# Digital_Input2.net
KiCad netlist of a schematic drawn in Altium Designer
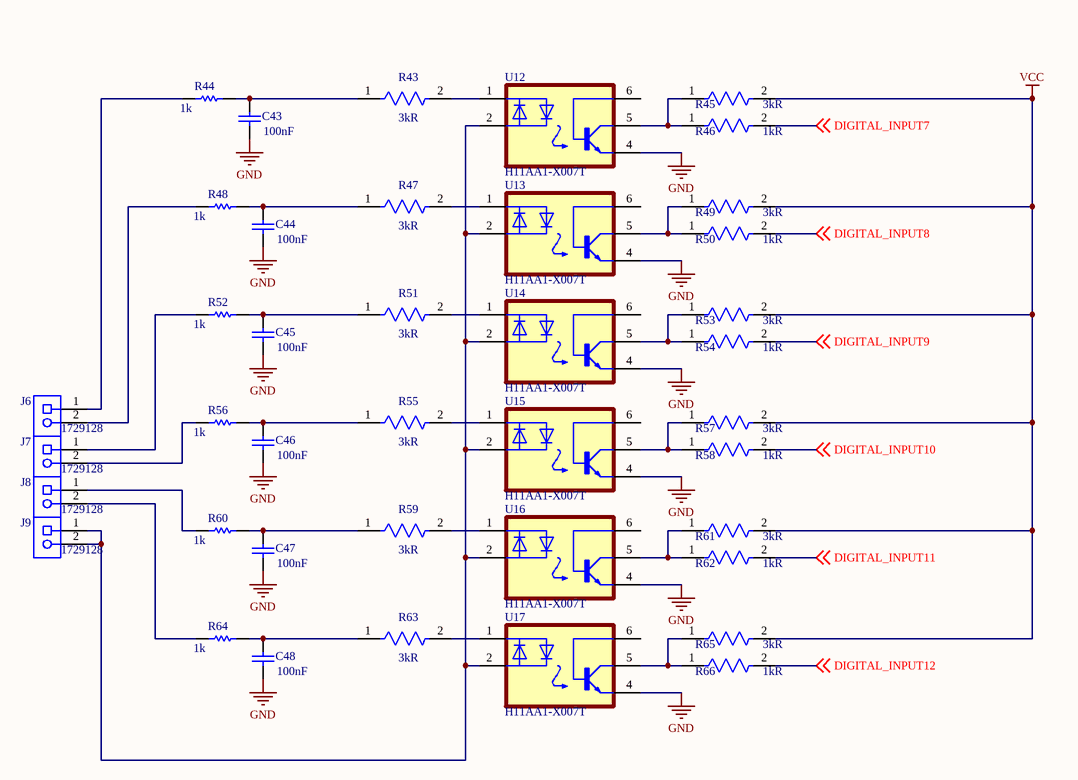
[diagram p0: Digital_Input2.SchDoc]

(export (version "E")
  (design (tool "Eeschema 10.0.6"))
  (components
    (comp (ref "C43")
      (value "100nF")
      (footprint "CAPC1608X87X35NL15T15")
      (fields (field (name "MANUFACTURER") "Kemet") (field (name "PART NUMBER") "C0603T104K3RACTU"))
      (libsource (lib "Altium Content Vault") (part "CAP"))
    )
    (comp (ref "C44")
      (value "100nF")
      (footprint "CAPC1608X87X35NL15T15")
      (fields (field (name "MANUFACTURER") "Kemet") (field (name "PART NUMBER") "C0603T104K3RACTU"))
      (libsource (lib "Altium Content Vault") (part "CAP"))
    )
    (comp (ref "C45")
      (value "100nF")
      (footprint "CAPC1608X87X35NL15T15")
      (fields (field (name "MANUFACTURER") "Kemet") (field (name "PART NUMBER") "C0603T104K3RACTU"))
      (libsource (lib "Altium Content Vault") (part "CAP"))
    )
    (comp (ref "C46")
      (value "100nF")
      (footprint "CAPC1608X87X35NL15T15")
      (fields (field (name "MANUFACTURER") "Kemet") (field (name "PART NUMBER") "C0603T104K3RACTU"))
      (libsource (lib "Altium Content Vault") (part "CAP"))
    )
    (comp (ref "C47")
      (value "100nF")
      (footprint "CAPC1608X87X35NL15T15")
      (fields (field (name "MANUFACTURER") "Kemet") (field (name "PART NUMBER") "C0603T104K3RACTU"))
      (libsource (lib "Altium Content Vault") (part "CAP"))
    )
    (comp (ref "C48")
      (value "100nF")
      (footprint "CAPC1608X87X35NL15T15")
      (fields (field (name "MANUFACTURER") "Kemet") (field (name "PART NUMBER") "C0603T104K3RACTU"))
      (libsource (lib "Altium Content Vault") (part "CAP"))
    )
    (comp (ref "J6")
      (value "1729128")
      (footprint "PHOE-1729128-2_V")
      (description "PCB Terminal Block, 13.5 A, 400 V, 2-Pin THD, RoHS, Bulk")
      (fields (field (name "MANUFACTURER") "Phoenix Contact"))
      (libsource (lib "Altium Content Vault") (part "CN-2P-F-R2"))
    )
    (comp (ref "J7")
      (value "1729128")
      (footprint "PHOE-1729128-2_V")
      (description "PCB Terminal Block, 13.5 A, 400 V, 2-Pin THD, RoHS, Bulk")
      (fields (field (name "MANUFACTURER") "Phoenix Contact"))
      (libsource (lib "Altium Content Vault") (part "CN-2P-F-R2"))
    )
    (comp (ref "J8")
      (value "1729128")
      (footprint "PHOE-1729128-2_V")
      (description "PCB Terminal Block, 13.5 A, 400 V, 2-Pin THD, RoHS, Bulk")
      (fields (field (name "MANUFACTURER") "Phoenix Contact"))
      (libsource (lib "Altium Content Vault") (part "CN-2P-F-R2"))
    )
    (comp (ref "J9")
      (value "1729128")
      (footprint "PHOE-1729128-2_V")
      (description "PCB Terminal Block, 13.5 A, 400 V, 2-Pin THD, RoHS, Bulk")
      (fields (field (name "MANUFACTURER") "Phoenix Contact"))
      (libsource (lib "Altium Content Vault") (part "CN-2P-F-R2"))
    )
    (comp (ref "R43")
      (value "CRCW06033K00FKEA")
      (footprint "FP-CRCW0603-e3-IPC_A")
      (description "RES Thick Film, 3kΩ, 1%, 0.1W, 100ppm/°C, 0603")
      (fields (field (name "RESISTANCE") "3kR") (field (name "TOLERANCE") "1%"))
      (libsource (lib "Altium Content Vault") (part "1029c3af85768c4190bb7ad29bc67b5"))
    )
    (comp (ref "R44")
      (value "1k")
      (footprint "RESC1608X55X25LL10T15")
      (fields (field (name "PART NUMBER") "RT0603DRE071KL") (field (name "MANUFACTURER") "Yageo"))
      (libsource (lib "Altium Content Vault") (part "RES"))
    )
    (comp (ref "R45")
      (value "CRCW06033K00FKEA")
      (footprint "FP-CRCW0603-e3-IPC_A")
      (description "RES Thick Film, 3kΩ, 1%, 0.1W, 100ppm/°C, 0603")
      (fields (field (name "RESISTANCE") "3kR") (field (name "TOLERANCE") "1%"))
      (libsource (lib "Altium Content Vault") (part "1029c3af85768c4190bb7ad29bc67b5"))
    )
    (comp (ref "R46")
      (value "RC0603FR-071KL")
      (footprint "FP-RC0603-0_55-IPC_C")
      (description "RES 1K OHM 1% 1/10W 0603")
      (fields (field (name "RESISTANCE") "1kR") (field (name "TOLERANCE") "1%"))
      (libsource (lib "Altium Content Vault") (part "1029c3af85768c4190bb7ad29bc67b5"))
    )
    (comp (ref "R47")
      (value "CRCW06033K00FKEA")
      (footprint "FP-CRCW0603-e3-IPC_A")
      (description "RES Thick Film, 3kΩ, 1%, 0.1W, 100ppm/°C, 0603")
      (fields (field (name "RESISTANCE") "3kR") (field (name "TOLERANCE") "1%"))
      (libsource (lib "Altium Content Vault") (part "1029c3af85768c4190bb7ad29bc67b5"))
    )
    (comp (ref "R48")
      (value "1k")
      (footprint "RESC1608X55X25LL10T15")
      (fields (field (name "PART NUMBER") "RT0603DRE071KL") (field (name "MANUFACTURER") "Yageo"))
      (libsource (lib "Altium Content Vault") (part "RES"))
    )
    (comp (ref "R49")
      (value "CRCW06033K00FKEA")
      (footprint "FP-CRCW0603-e3-IPC_A")
      (description "RES Thick Film, 3kΩ, 1%, 0.1W, 100ppm/°C, 0603")
      (fields (field (name "RESISTANCE") "3kR") (field (name "TOLERANCE") "1%"))
      (libsource (lib "Altium Content Vault") (part "1029c3af85768c4190bb7ad29bc67b5"))
    )
    (comp (ref "R50")
      (value "RC0603FR-071KL")
      (footprint "FP-RC0603-0_55-IPC_C")
      (description "RES 1K OHM 1% 1/10W 0603")
      (fields (field (name "RESISTANCE") "1kR") (field (name "TOLERANCE") "1%"))
      (libsource (lib "Altium Content Vault") (part "1029c3af85768c4190bb7ad29bc67b5"))
    )
    (comp (ref "R51")
      (value "CRCW06033K00FKEA")
      (footprint "FP-CRCW0603-e3-IPC_A")
      (description "RES Thick Film, 3kΩ, 1%, 0.1W, 100ppm/°C, 0603")
      (fields (field (name "RESISTANCE") "3kR") (field (name "TOLERANCE") "1%"))
      (libsource (lib "Altium Content Vault") (part "1029c3af85768c4190bb7ad29bc67b5"))
    )
    (comp (ref "R52")
      (value "1k")
      (footprint "RESC1608X55X25LL10T15")
      (fields (field (name "PART NUMBER") "RT0603DRE071KL") (field (name "MANUFACTURER") "Yageo"))
      (libsource (lib "Altium Content Vault") (part "RES"))
    )
    (comp (ref "R53")
      (value "CRCW06033K00FKEA")
      (footprint "FP-CRCW0603-e3-IPC_A")
      (description "RES Thick Film, 3kΩ, 1%, 0.1W, 100ppm/°C, 0603")
      (fields (field (name "RESISTANCE") "3kR") (field (name "TOLERANCE") "1%"))
      (libsource (lib "Altium Content Vault") (part "1029c3af85768c4190bb7ad29bc67b5"))
    )
    (comp (ref "R54")
      (value "RC0603FR-071KL")
      (footprint "FP-RC0603-0_55-IPC_C")
      (description "RES 1K OHM 1% 1/10W 0603")
      (fields (field (name "RESISTANCE") "1kR") (field (name "TOLERANCE") "1%"))
      (libsource (lib "Altium Content Vault") (part "1029c3af85768c4190bb7ad29bc67b5"))
    )
    (comp (ref "R55")
      (value "CRCW06033K00FKEA")
      (footprint "FP-CRCW0603-e3-IPC_A")
      (description "RES Thick Film, 3kΩ, 1%, 0.1W, 100ppm/°C, 0603")
      (fields (field (name "RESISTANCE") "3kR") (field (name "TOLERANCE") "1%"))
      (libsource (lib "Altium Content Vault") (part "1029c3af85768c4190bb7ad29bc67b5"))
    )
    (comp (ref "R56")
      (value "1k")
      (footprint "RESC1608X55X25LL10T15")
      (fields (field (name "PART NUMBER") "RT0603DRE071KL") (field (name "MANUFACTURER") "Yageo"))
      (libsource (lib "Altium Content Vault") (part "RES"))
    )
    (comp (ref "R57")
      (value "CRCW06033K00FKEA")
      (footprint "FP-CRCW0603-e3-IPC_A")
      (description "RES Thick Film, 3kΩ, 1%, 0.1W, 100ppm/°C, 0603")
      (fields (field (name "RESISTANCE") "3kR") (field (name "TOLERANCE") "1%"))
      (libsource (lib "Altium Content Vault") (part "1029c3af85768c4190bb7ad29bc67b5"))
    )
    (comp (ref "R58")
      (value "RC0603FR-071KL")
      (footprint "FP-RC0603-0_55-IPC_C")
      (description "RES 1K OHM 1% 1/10W 0603")
      (fields (field (name "RESISTANCE") "1kR") (field (name "TOLERANCE") "1%"))
      (libsource (lib "Altium Content Vault") (part "1029c3af85768c4190bb7ad29bc67b5"))
    )
    (comp (ref "R59")
      (value "CRCW06033K00FKEA")
      (footprint "FP-CRCW0603-e3-IPC_A")
      (description "RES Thick Film, 3kΩ, 1%, 0.1W, 100ppm/°C, 0603")
      (fields (field (name "RESISTANCE") "3kR") (field (name "TOLERANCE") "1%"))
      (libsource (lib "Altium Content Vault") (part "1029c3af85768c4190bb7ad29bc67b5"))
    )
    (comp (ref "R60")
      (value "1k")
      (footprint "RESC1608X55X25LL10T15")
      (fields (field (name "PART NUMBER") "RT0603DRE071KL") (field (name "MANUFACTURER") "Yageo"))
      (libsource (lib "Altium Content Vault") (part "RES"))
    )
    (comp (ref "R61")
      (value "CRCW06033K00FKEA")
      (footprint "FP-CRCW0603-e3-IPC_A")
      (description "RES Thick Film, 3kΩ, 1%, 0.1W, 100ppm/°C, 0603")
      (fields (field (name "RESISTANCE") "3kR") (field (name "TOLERANCE") "1%"))
      (libsource (lib "Altium Content Vault") (part "1029c3af85768c4190bb7ad29bc67b5"))
    )
    (comp (ref "R62")
      (value "RC0603FR-071KL")
      (footprint "FP-RC0603-0_55-IPC_C")
      (description "RES 1K OHM 1% 1/10W 0603")
      (fields (field (name "RESISTANCE") "1kR") (field (name "TOLERANCE") "1%"))
      (libsource (lib "Altium Content Vault") (part "1029c3af85768c4190bb7ad29bc67b5"))
    )
    (comp (ref "R63")
      (value "CRCW06033K00FKEA")
      (footprint "FP-CRCW0603-e3-IPC_A")
      (description "RES Thick Film, 3kΩ, 1%, 0.1W, 100ppm/°C, 0603")
      (fields (field (name "RESISTANCE") "3kR") (field (name "TOLERANCE") "1%"))
      (libsource (lib "Altium Content Vault") (part "1029c3af85768c4190bb7ad29bc67b5"))
    )
    (comp (ref "R64")
      (value "1k")
      (footprint "RESC1608X55X25LL10T15")
      (fields (field (name "PART NUMBER") "RT0603DRE071KL") (field (name "MANUFACTURER") "Yageo"))
      (libsource (lib "Altium Content Vault") (part "RES"))
    )
    (comp (ref "R65")
      (value "CRCW06033K00FKEA")
      (footprint "FP-CRCW0603-e3-IPC_A")
      (description "RES Thick Film, 3kΩ, 1%, 0.1W, 100ppm/°C, 0603")
      (fields (field (name "RESISTANCE") "3kR") (field (name "TOLERANCE") "1%"))
      (libsource (lib "Altium Content Vault") (part "1029c3af85768c4190bb7ad29bc67b5"))
    )
    (comp (ref "R66")
      (value "RC0603FR-071KL")
      (footprint "FP-RC0603-0_55-IPC_C")
      (description "RES 1K OHM 1% 1/10W 0603")
      (fields (field (name "RESISTANCE") "1kR") (field (name "TOLERANCE") "1%"))
      (libsource (lib "Altium Content Vault") (part "1029c3af85768c4190bb7ad29bc67b5"))
    )
    (comp (ref "U12")
      (value "H11AA1-X007T")
      (footprint "SOIC254P1030X460-6N")
      (description "H11AA1 Series Single Channel 30V 5300 Vrms SMT Phototransistor Optocoupler DIP-6")
      (fields (field (name "MF") "Vishay Semiconductor"))
      (libsource (lib "H11AA1-X007T") (part "H11AA1-X007T"))
    )
    (comp (ref "U13")
      (value "H11AA1-X007T")
      (footprint "SOIC254P1030X460-6N")
      (description "H11AA1 Series Single Channel 30V 5300 Vrms SMT Phototransistor Optocoupler DIP-6")
      (fields (field (name "MF") "Vishay Semiconductor"))
      (libsource (lib "H11AA1-X007T") (part "H11AA1-X007T"))
    )
    (comp (ref "U14")
      (value "H11AA1-X007T")
      (footprint "SOIC254P1030X460-6N")
      (description "H11AA1 Series Single Channel 30V 5300 Vrms SMT Phototransistor Optocoupler DIP-6")
      (fields (field (name "MF") "Vishay Semiconductor"))
      (libsource (lib "H11AA1-X007T") (part "H11AA1-X007T"))
    )
    (comp (ref "U15")
      (value "H11AA1-X007T")
      (footprint "SOIC254P1030X460-6N")
      (description "H11AA1 Series Single Channel 30V 5300 Vrms SMT Phototransistor Optocoupler DIP-6")
      (fields (field (name "MF") "Vishay Semiconductor"))
      (libsource (lib "H11AA1-X007T") (part "H11AA1-X007T"))
    )
    (comp (ref "U16")
      (value "H11AA1-X007T")
      (footprint "SOIC254P1030X460-6N")
      (description "H11AA1 Series Single Channel 30V 5300 Vrms SMT Phototransistor Optocoupler DIP-6")
      (fields (field (name "MF") "Vishay Semiconductor"))
      (libsource (lib "H11AA1-X007T") (part "H11AA1-X007T"))
    )
    (comp (ref "U17")
      (value "H11AA1-X007T")
      (footprint "SOIC254P1030X460-6N")
      (description "H11AA1 Series Single Channel 30V 5300 Vrms SMT Phototransistor Optocoupler DIP-6")
      (fields (field (name "MF") "Vishay Semiconductor"))
      (libsource (lib "H11AA1-X007T") (part "H11AA1-X007T"))
    )
  )
  (nets
    (net (code "1") (name "DIGITAL_INPUT7") (class "Default")
      (node (ref "R46") (pin "2") (pinfunction "2_2") (pintype "passive"))
    )
    (net (code "2") (name "DIGITAL_INPUT8") (class "Default")
      (node (ref "R50") (pin "2") (pinfunction "2_2") (pintype "passive"))
    )
    (net (code "3") (name "DIGITAL_INPUT9") (class "Default")
      (node (ref "R54") (pin "2") (pinfunction "2_2") (pintype "passive"))
    )
    (net (code "4") (name "DIGITAL_INPUT10") (class "Default")
      (node (ref "R58") (pin "2") (pinfunction "2_2") (pintype "passive"))
    )
    (net (code "5") (name "DIGITAL_INPUT11") (class "Default")
      (node (ref "R62") (pin "2") (pinfunction "2_2") (pintype "passive"))
    )
    (net (code "6") (name "DIGITAL_INPUT12") (class "Default")
      (node (ref "R66") (pin "2") (pinfunction "2_2") (pintype "passive"))
    )
    (net (code "7") (name "GND") (class "Default")
      (node (ref "C43") (pin "1") (pinfunction "1_1") (pintype "passive"))
      (node (ref "C44") (pin "1") (pinfunction "1_1") (pintype "passive"))
      (node (ref "C45") (pin "1") (pinfunction "1_1") (pintype "passive"))
      (node (ref "C46") (pin "1") (pinfunction "1_1") (pintype "passive"))
      (node (ref "C47") (pin "1") (pinfunction "1_1") (pintype "passive"))
      (node (ref "C48") (pin "1") (pinfunction "1_1") (pintype "passive"))
      (node (ref "U12") (pin "4") (pinfunction "E_4") (pintype "passive"))
      (node (ref "U13") (pin "4") (pinfunction "E_4") (pintype "passive"))
      (node (ref "U14") (pin "4") (pinfunction "E_4") (pintype "passive"))
      (node (ref "U15") (pin "4") (pinfunction "E_4") (pintype "passive"))
      (node (ref "U16") (pin "4") (pinfunction "E_4") (pintype "passive"))
      (node (ref "U17") (pin "4") (pinfunction "E_4") (pintype "passive"))
    )
    (net (code "8") (name "Net-(C43-Pad2)") (class "Default")
      (node (ref "C43") (pin "2") (pinfunction "2_2") (pintype "passive"))
      (node (ref "R43") (pin "1") (pinfunction "1_1") (pintype "passive"))
      (node (ref "R44") (pin "2") (pinfunction "2_2") (pintype "passive"))
    )
    (net (code "9") (name "Net-(C44-Pad2)") (class "Default")
      (node (ref "C44") (pin "2") (pinfunction "2_2") (pintype "passive"))
      (node (ref "R47") (pin "1") (pinfunction "1_1") (pintype "passive"))
      (node (ref "R48") (pin "2") (pinfunction "2_2") (pintype "passive"))
    )
    (net (code "10") (name "Net-(C45-Pad2)") (class "Default")
      (node (ref "C45") (pin "2") (pinfunction "2_2") (pintype "passive"))
      (node (ref "R51") (pin "1") (pinfunction "1_1") (pintype "passive"))
      (node (ref "R52") (pin "2") (pinfunction "2_2") (pintype "passive"))
    )
    (net (code "11") (name "Net-(C46-Pad2)") (class "Default")
      (node (ref "C46") (pin "2") (pinfunction "2_2") (pintype "passive"))
      (node (ref "R55") (pin "1") (pinfunction "1_1") (pintype "passive"))
      (node (ref "R56") (pin "2") (pinfunction "2_2") (pintype "passive"))
    )
    (net (code "12") (name "Net-(C47-Pad2)") (class "Default")
      (node (ref "C47") (pin "2") (pinfunction "2_2") (pintype "passive"))
      (node (ref "R59") (pin "1") (pinfunction "1_1") (pintype "passive"))
      (node (ref "R60") (pin "2") (pinfunction "2_2") (pintype "passive"))
    )
    (net (code "13") (name "Net-(C48-Pad2)") (class "Default")
      (node (ref "C48") (pin "2") (pinfunction "2_2") (pintype "passive"))
      (node (ref "R63") (pin "1") (pinfunction "1_1") (pintype "passive"))
      (node (ref "R64") (pin "2") (pinfunction "2_2") (pintype "passive"))
    )
    (net (code "14") (name "Net-(J6-Pad1)") (class "Default")
      (node (ref "J6") (pin "1") (pinfunction "1_1") (pintype "passive"))
      (node (ref "R44") (pin "1") (pinfunction "1_1") (pintype "passive"))
    )
    (net (code "15") (name "Net-(J6-Pad2)") (class "Default")
      (node (ref "J6") (pin "2") (pinfunction "2_2") (pintype "passive"))
      (node (ref "R48") (pin "1") (pinfunction "1_1") (pintype "passive"))
    )
    (net (code "16") (name "Net-(J7-Pad1)") (class "Default")
      (node (ref "J7") (pin "1") (pinfunction "1_1") (pintype "passive"))
      (node (ref "R52") (pin "1") (pinfunction "1_1") (pintype "passive"))
    )
    (net (code "17") (name "Net-(J7-Pad2)") (class "Default")
      (node (ref "J7") (pin "2") (pinfunction "2_2") (pintype "passive"))
      (node (ref "R56") (pin "1") (pinfunction "1_1") (pintype "passive"))
    )
    (net (code "18") (name "Net-(J8-Pad1)") (class "Default")
      (node (ref "J8") (pin "1") (pinfunction "1_1") (pintype "passive"))
      (node (ref "R60") (pin "1") (pinfunction "1_1") (pintype "passive"))
    )
    (net (code "19") (name "Net-(J8-Pad2)") (class "Default")
      (node (ref "J8") (pin "2") (pinfunction "2_2") (pintype "passive"))
      (node (ref "R64") (pin "1") (pinfunction "1_1") (pintype "passive"))
    )
    (net (code "20") (name "Net-(U12-A{slash}C)") (class "Default")
      (node (ref "R43") (pin "2") (pinfunction "2_2") (pintype "passive"))
      (node (ref "U12") (pin "1") (pinfunction "A/C_1") (pintype "passive"))
    )
    (net (code "21") (name "Net-(U12-C)") (class "Default")
      (node (ref "R45") (pin "1") (pinfunction "1_1") (pintype "passive"))
      (node (ref "R46") (pin "1") (pinfunction "1_1") (pintype "passive"))
      (node (ref "U12") (pin "5") (pinfunction "C_5") (pintype "passive"))
    )
    (net (code "22") (name "Net-(U12-C{slash}A)") (class "Default")
      (node (ref "J9") (pin "1") (pinfunction "1_1") (pintype "passive"))
      (node (ref "J9") (pin "2") (pinfunction "2_2") (pintype "passive"))
      (node (ref "U12") (pin "2") (pinfunction "C/A_2") (pintype "passive"))
      (node (ref "U13") (pin "2") (pinfunction "C/A_2") (pintype "passive"))
      (node (ref "U14") (pin "2") (pinfunction "C/A_2") (pintype "passive"))
      (node (ref "U15") (pin "2") (pinfunction "C/A_2") (pintype "passive"))
      (node (ref "U16") (pin "2") (pinfunction "C/A_2") (pintype "passive"))
      (node (ref "U17") (pin "2") (pinfunction "C/A_2") (pintype "passive"))
    )
    (net (code "23") (name "Net-(U13-A{slash}C)") (class "Default")
      (node (ref "R47") (pin "2") (pinfunction "2_2") (pintype "passive"))
      (node (ref "U13") (pin "1") (pinfunction "A/C_1") (pintype "passive"))
    )
    (net (code "24") (name "Net-(U13-C)") (class "Default")
      (node (ref "R49") (pin "1") (pinfunction "1_1") (pintype "passive"))
      (node (ref "R50") (pin "1") (pinfunction "1_1") (pintype "passive"))
      (node (ref "U13") (pin "5") (pinfunction "C_5") (pintype "passive"))
    )
    (net (code "25") (name "Net-(U14-A{slash}C)") (class "Default")
      (node (ref "R51") (pin "2") (pinfunction "2_2") (pintype "passive"))
      (node (ref "U14") (pin "1") (pinfunction "A/C_1") (pintype "passive"))
    )
    (net (code "26") (name "Net-(U14-C)") (class "Default")
      (node (ref "R53") (pin "1") (pinfunction "1_1") (pintype "passive"))
      (node (ref "R54") (pin "1") (pinfunction "1_1") (pintype "passive"))
      (node (ref "U14") (pin "5") (pinfunction "C_5") (pintype "passive"))
    )
    (net (code "27") (name "Net-(U15-A{slash}C)") (class "Default")
      (node (ref "R55") (pin "2") (pinfunction "2_2") (pintype "passive"))
      (node (ref "U15") (pin "1") (pinfunction "A/C_1") (pintype "passive"))
    )
    (net (code "28") (name "Net-(U15-C)") (class "Default")
      (node (ref "R57") (pin "1") (pinfunction "1_1") (pintype "passive"))
      (node (ref "R58") (pin "1") (pinfunction "1_1") (pintype "passive"))
      (node (ref "U15") (pin "5") (pinfunction "C_5") (pintype "passive"))
    )
    (net (code "29") (name "Net-(U16-A{slash}C)") (class "Default")
      (node (ref "R59") (pin "2") (pinfunction "2_2") (pintype "passive"))
      (node (ref "U16") (pin "1") (pinfunction "A/C_1") (pintype "passive"))
    )
    (net (code "30") (name "Net-(U16-C)") (class "Default")
      (node (ref "R61") (pin "1") (pinfunction "1_1") (pintype "passive"))
      (node (ref "R62") (pin "1") (pinfunction "1_1") (pintype "passive"))
      (node (ref "U16") (pin "5") (pinfunction "C_5") (pintype "passive"))
    )
    (net (code "31") (name "Net-(U17-A{slash}C)") (class "Default")
      (node (ref "R63") (pin "2") (pinfunction "2_2") (pintype "passive"))
      (node (ref "U17") (pin "1") (pinfunction "A/C_1") (pintype "passive"))
    )
    (net (code "32") (name "Net-(U17-C)") (class "Default")
      (node (ref "R65") (pin "1") (pinfunction "1_1") (pintype "passive"))
      (node (ref "R66") (pin "1") (pinfunction "1_1") (pintype "passive"))
      (node (ref "U17") (pin "5") (pinfunction "C_5") (pintype "passive"))
    )
    (net (code "33") (name "VCC") (class "Default")
      (node (ref "R45") (pin "2") (pinfunction "2_2") (pintype "passive"))
      (node (ref "R49") (pin "2") (pinfunction "2_2") (pintype "passive"))
      (node (ref "R53") (pin "2") (pinfunction "2_2") (pintype "passive"))
      (node (ref "R57") (pin "2") (pinfunction "2_2") (pintype "passive"))
      (node (ref "R61") (pin "2") (pinfunction "2_2") (pintype "passive"))
      (node (ref "R65") (pin "2") (pinfunction "2_2") (pintype "passive"))
    )
    (net (code "34") (name "unconnected-(U12-B-Pad6)") (class "Default")
      (node (ref "U12") (pin "6") (pinfunction "B_6") (pintype "passive"))
    )
    (net (code "35") (name "unconnected-(U13-B-Pad6)") (class "Default")
      (node (ref "U13") (pin "6") (pinfunction "B_6") (pintype "passive"))
    )
    (net (code "36") (name "unconnected-(U14-B-Pad6)") (class "Default")
      (node (ref "U14") (pin "6") (pinfunction "B_6") (pintype "passive"))
    )
    (net (code "37") (name "unconnected-(U15-B-Pad6)") (class "Default")
      (node (ref "U15") (pin "6") (pinfunction "B_6") (pintype "passive"))
    )
    (net (code "38") (name "unconnected-(U16-B-Pad6)") (class "Default")
      (node (ref "U16") (pin "6") (pinfunction "B_6") (pintype "passive"))
    )
    (net (code "39") (name "unconnected-(U17-B-Pad6)") (class "Default")
      (node (ref "U17") (pin "6") (pinfunction "B_6") (pintype "passive"))
    )
  )
)
